# VDD.net
KiCad netlist of a schematic drawn in Altium Designer
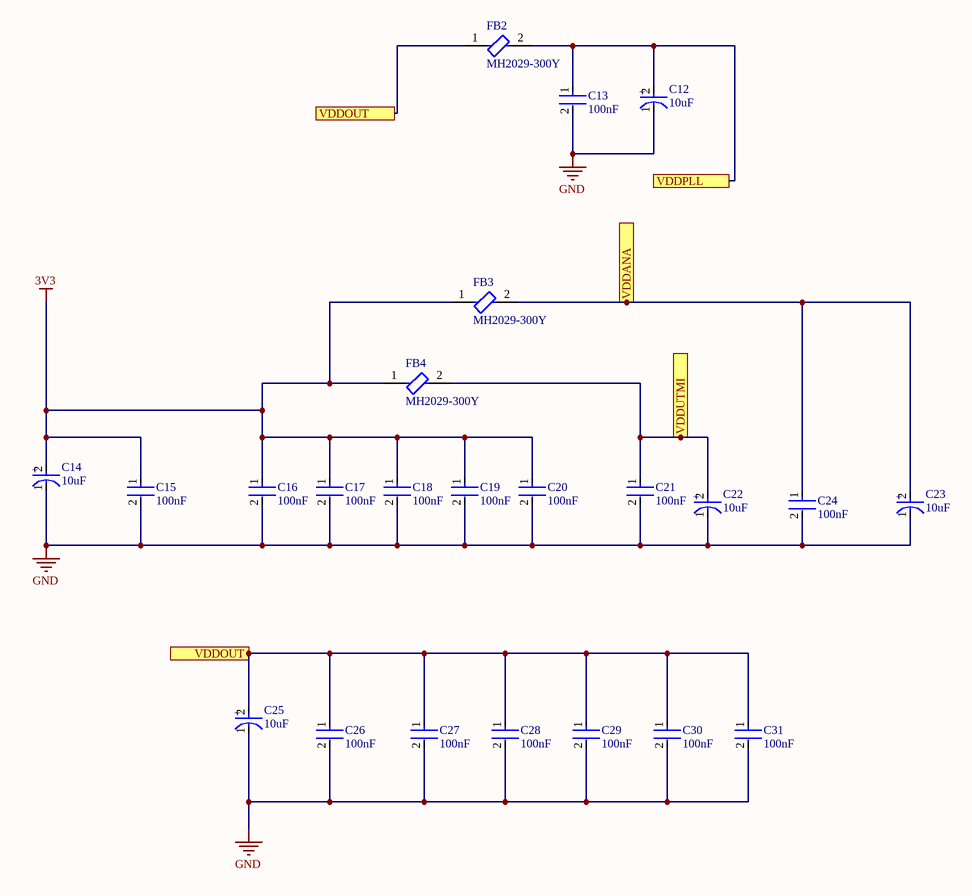
[diagram p0:  VDD.SchDoc]

(export (version "E")
  (design (tool "Eeschema 10.0.6"))
  (components
    (comp (ref "C12")
      (value "10uF")
      (footprint "FP-TAJP-MFG")
      (description "10uF 10V  ±20% 6Ω 0805  SMD Tantalum Capacitor")
      (fields (field (name "TOLERANCE") "20%") (field (name "VOLTAGE") "10V"))
      (libsource (lib "Altium Content Vault") (part "a00bbbee19879c290e62620ae7e47b1"))
    )
    (comp (ref "C13")
      (value "100nF")
      (footprint "FP-0805-L_2_01_0_2-W_1_25-IPC_B")
      (description "General Purpose Ceramic Capacitor, 0805, 100nF, 10%, X7R, 15%, 100V")
      (fields (field (name "VOLTAGE") "100V") (field (name "TOLERANCE") "10%"))
      (libsource (lib "Altium Content Vault") (part "b4654b650e69147ec39a6b967a45e02"))
    )
    (comp (ref "C14")
      (value "10uF")
      (footprint "FP-TAJP-MFG")
      (description "10uF 10V  ±20% 6Ω 0805  SMD Tantalum Capacitor")
      (fields (field (name "TOLERANCE") "20%") (field (name "VOLTAGE") "10V"))
      (libsource (lib "Altium Content Vault") (part "a00bbbee19879c290e62620ae7e47b1"))
    )
    (comp (ref "C15")
      (value "100nF")
      (footprint "FP-0805-L_2_01_0_2-W_1_25-IPC_B")
      (description "General Purpose Ceramic Capacitor, 0805, 100nF, 10%, X7R, 15%, 100V")
      (fields (field (name "VOLTAGE") "100V") (field (name "TOLERANCE") "10%"))
      (libsource (lib "Altium Content Vault") (part "b4654b650e69147ec39a6b967a45e02"))
    )
    (comp (ref "C16")
      (value "100nF")
      (footprint "FP-0805-L_2_01_0_2-W_1_25-IPC_B")
      (description "General Purpose Ceramic Capacitor, 0805, 100nF, 10%, X7R, 15%, 100V")
      (fields (field (name "VOLTAGE") "100V") (field (name "TOLERANCE") "10%"))
      (libsource (lib "Altium Content Vault") (part "b4654b650e69147ec39a6b967a45e02"))
    )
    (comp (ref "C17")
      (value "100nF")
      (footprint "FP-0805-L_2_01_0_2-W_1_25-IPC_B")
      (description "General Purpose Ceramic Capacitor, 0805, 100nF, 10%, X7R, 15%, 100V")
      (fields (field (name "VOLTAGE") "100V") (field (name "TOLERANCE") "10%"))
      (libsource (lib "Altium Content Vault") (part "b4654b650e69147ec39a6b967a45e02"))
    )
    (comp (ref "C18")
      (value "100nF")
      (footprint "FP-0805-L_2_01_0_2-W_1_25-IPC_B")
      (description "General Purpose Ceramic Capacitor, 0805, 100nF, 10%, X7R, 15%, 100V")
      (fields (field (name "VOLTAGE") "100V") (field (name "TOLERANCE") "10%"))
      (libsource (lib "Altium Content Vault") (part "b4654b650e69147ec39a6b967a45e02"))
    )
    (comp (ref "C19")
      (value "100nF")
      (footprint "FP-0805-L_2_01_0_2-W_1_25-IPC_B")
      (description "General Purpose Ceramic Capacitor, 0805, 100nF, 10%, X7R, 15%, 100V")
      (fields (field (name "VOLTAGE") "100V") (field (name "TOLERANCE") "10%"))
      (libsource (lib "Altium Content Vault") (part "b4654b650e69147ec39a6b967a45e02"))
    )
    (comp (ref "C20")
      (value "100nF")
      (footprint "FP-0805-L_2_01_0_2-W_1_25-IPC_B")
      (description "General Purpose Ceramic Capacitor, 0805, 100nF, 10%, X7R, 15%, 100V")
      (fields (field (name "VOLTAGE") "100V") (field (name "TOLERANCE") "10%"))
      (libsource (lib "Altium Content Vault") (part "b4654b650e69147ec39a6b967a45e02"))
    )
    (comp (ref "C21")
      (value "100nF")
      (footprint "FP-0805-L_2_01_0_2-W_1_25-IPC_B")
      (description "General Purpose Ceramic Capacitor, 0805, 100nF, 10%, X7R, 15%, 100V")
      (fields (field (name "VOLTAGE") "100V") (field (name "TOLERANCE") "10%"))
      (libsource (lib "Altium Content Vault") (part "b4654b650e69147ec39a6b967a45e02"))
    )
    (comp (ref "C22")
      (value "10uF")
      (footprint "FP-TAJP-MFG")
      (description "10uF 10V  ±20% 6Ω 0805  SMD Tantalum Capacitor")
      (fields (field (name "TOLERANCE") "20%") (field (name "VOLTAGE") "10V"))
      (libsource (lib "Altium Content Vault") (part "a00bbbee19879c290e62620ae7e47b1"))
    )
    (comp (ref "C23")
      (value "10uF")
      (footprint "FP-TAJP-MFG")
      (description "10uF 10V  ±20% 6Ω 0805  SMD Tantalum Capacitor")
      (fields (field (name "TOLERANCE") "20%") (field (name "VOLTAGE") "10V"))
      (libsource (lib "Altium Content Vault") (part "a00bbbee19879c290e62620ae7e47b1"))
    )
    (comp (ref "C24")
      (value "100nF")
      (footprint "FP-0805-L_2_01_0_2-W_1_25-IPC_B")
      (description "General Purpose Ceramic Capacitor, 0805, 100nF, 10%, X7R, 15%, 100V")
      (fields (field (name "VOLTAGE") "100V") (field (name "TOLERANCE") "10%"))
      (libsource (lib "Altium Content Vault") (part "b4654b650e69147ec39a6b967a45e02"))
    )
    (comp (ref "C25")
      (value "10uF")
      (footprint "FP-TAJP-MFG")
      (description "10uF 10V  ±20% 6Ω 0805  SMD Tantalum Capacitor")
      (fields (field (name "TOLERANCE") "20%") (field (name "VOLTAGE") "10V"))
      (libsource (lib "Altium Content Vault") (part "a00bbbee19879c290e62620ae7e47b1"))
    )
    (comp (ref "C26")
      (value "100nF")
      (footprint "FP-0805-L_2_01_0_2-W_1_25-IPC_B")
      (description "General Purpose Ceramic Capacitor, 0805, 100nF, 10%, X7R, 15%, 100V")
      (fields (field (name "VOLTAGE") "100V") (field (name "TOLERANCE") "10%"))
      (libsource (lib "Altium Content Vault") (part "b4654b650e69147ec39a6b967a45e02"))
    )
    (comp (ref "C27")
      (value "100nF")
      (footprint "FP-0805-L_2_01_0_2-W_1_25-IPC_B")
      (description "General Purpose Ceramic Capacitor, 0805, 100nF, 10%, X7R, 15%, 100V")
      (fields (field (name "VOLTAGE") "100V") (field (name "TOLERANCE") "10%"))
      (libsource (lib "Altium Content Vault") (part "b4654b650e69147ec39a6b967a45e02"))
    )
    (comp (ref "C28")
      (value "100nF")
      (footprint "FP-0805-L_2_01_0_2-W_1_25-IPC_B")
      (description "General Purpose Ceramic Capacitor, 0805, 100nF, 10%, X7R, 15%, 100V")
      (fields (field (name "VOLTAGE") "100V") (field (name "TOLERANCE") "10%"))
      (libsource (lib "Altium Content Vault") (part "b4654b650e69147ec39a6b967a45e02"))
    )
    (comp (ref "C29")
      (value "100nF")
      (footprint "FP-0805-L_2_01_0_2-W_1_25-IPC_B")
      (description "General Purpose Ceramic Capacitor, 0805, 100nF, 10%, X7R, 15%, 100V")
      (fields (field (name "VOLTAGE") "100V") (field (name "TOLERANCE") "10%"))
      (libsource (lib "Altium Content Vault") (part "b4654b650e69147ec39a6b967a45e02"))
    )
    (comp (ref "C30")
      (value "100nF")
      (footprint "FP-0805-L_2_01_0_2-W_1_25-IPC_B")
      (description "General Purpose Ceramic Capacitor, 0805, 100nF, 10%, X7R, 15%, 100V")
      (fields (field (name "VOLTAGE") "100V") (field (name "TOLERANCE") "10%"))
      (libsource (lib "Altium Content Vault") (part "b4654b650e69147ec39a6b967a45e02"))
    )
    (comp (ref "C31")
      (value "100nF")
      (footprint "FP-0805-L_2_01_0_2-W_1_25-IPC_B")
      (description "General Purpose Ceramic Capacitor, 0805, 100nF, 10%, X7R, 15%, 100V")
      (fields (field (name "VOLTAGE") "100V") (field (name "TOLERANCE") "10%"))
      (libsource (lib "Altium Content Vault") (part "b4654b650e69147ec39a6b967a45e02"))
    )
    (comp (ref "FB2")
      (value "MH2029-300Y")
      (footprint "FP-MH2029-MFG")
      (description "FERRITE BEAD 30 OHM 0805 1LN")
      (fields
        (field (name "OCTOPART") "https://octopart.com/mh2029-300y-bourns-756929")
        (field (name "MANUFACTURER") "Bourns")
      )
      (libsource (lib "Altium Content Vault") (part "5f30dd21d616792df468990f7003faa"))
    )
    (comp (ref "FB3")
      (value "MH2029-300Y")
      (footprint "FP-MH2029-MFG")
      (description "FERRITE BEAD 30 OHM 0805 1LN")
      (fields
        (field (name "OCTOPART") "https://octopart.com/mh2029-300y-bourns-756929")
        (field (name "MANUFACTURER") "Bourns")
      )
      (libsource (lib "Altium Content Vault") (part "5f30dd21d616792df468990f7003faa"))
    )
    (comp (ref "FB4")
      (value "MH2029-300Y")
      (footprint "FP-MH2029-MFG")
      (description "FERRITE BEAD 30 OHM 0805 1LN")
      (fields
        (field (name "OCTOPART") "https://octopart.com/mh2029-300y-bourns-756929")
        (field (name "MANUFACTURER") "Bourns")
      )
      (libsource (lib "Altium Content Vault") (part "5f30dd21d616792df468990f7003faa"))
    )
  )
  (nets
    (net (code "1") (name "/VDDANA") (class "Default")
      (node (ref "C23") (pin "2") (pinfunction "A_2") (pintype "passive"))
      (node (ref "C24") (pin "1") (pinfunction "1_1") (pintype "passive"))
      (node (ref "FB3") (pin "2") (pinfunction "2_2") (pintype "passive"))
    )
    (net (code "2") (name "/VDDOUT") (class "Default")
      (node (ref "C25") (pin "2") (pinfunction "A_2") (pintype "passive"))
      (node (ref "C26") (pin "1") (pinfunction "1_1") (pintype "passive"))
      (node (ref "C27") (pin "1") (pinfunction "1_1") (pintype "passive"))
      (node (ref "C28") (pin "1") (pinfunction "1_1") (pintype "passive"))
      (node (ref "C29") (pin "1") (pinfunction "1_1") (pintype "passive"))
      (node (ref "C30") (pin "1") (pinfunction "1_1") (pintype "passive"))
      (node (ref "C31") (pin "1") (pinfunction "1_1") (pintype "passive"))
      (node (ref "FB2") (pin "1") (pinfunction "1_1") (pintype "passive"))
    )
    (net (code "3") (name "/VDDPLL") (class "Default")
      (node (ref "C12") (pin "2") (pinfunction "A_2") (pintype "passive"))
      (node (ref "C13") (pin "1") (pinfunction "1_1") (pintype "passive"))
      (node (ref "FB2") (pin "2") (pinfunction "2_2") (pintype "passive"))
    )
    (net (code "4") (name "/VDDUTMI") (class "Default")
      (node (ref "C21") (pin "1") (pinfunction "1_1") (pintype "passive"))
      (node (ref "C22") (pin "2") (pinfunction "A_2") (pintype "passive"))
      (node (ref "FB4") (pin "2") (pinfunction "2_2") (pintype "passive"))
    )
    (net (code "5") (name "3V3") (class "Default")
      (node (ref "C14") (pin "2") (pinfunction "A_2") (pintype "passive"))
      (node (ref "C15") (pin "1") (pinfunction "1_1") (pintype "passive"))
      (node (ref "C16") (pin "1") (pinfunction "1_1") (pintype "passive"))
      (node (ref "C17") (pin "1") (pinfunction "1_1") (pintype "passive"))
      (node (ref "C18") (pin "1") (pinfunction "1_1") (pintype "passive"))
      (node (ref "C19") (pin "1") (pinfunction "1_1") (pintype "passive"))
      (node (ref "C20") (pin "1") (pinfunction "1_1") (pintype "passive"))
      (node (ref "FB3") (pin "1") (pinfunction "1_1") (pintype "passive"))
      (node (ref "FB4") (pin "1") (pinfunction "1_1") (pintype "passive"))
    )
    (net (code "6") (name "GND") (class "Default")
      (node (ref "C12") (pin "1") (pinfunction "C_1") (pintype "passive"))
      (node (ref "C13") (pin "2") (pinfunction "2_2") (pintype "passive"))
      (node (ref "C14") (pin "1") (pinfunction "C_1") (pintype "passive"))
      (node (ref "C15") (pin "2") (pinfunction "2_2") (pintype "passive"))
      (node (ref "C16") (pin "2") (pinfunction "2_2") (pintype "passive"))
      (node (ref "C17") (pin "2") (pinfunction "2_2") (pintype "passive"))
      (node (ref "C18") (pin "2") (pinfunction "2_2") (pintype "passive"))
      (node (ref "C19") (pin "2") (pinfunction "2_2") (pintype "passive"))
      (node (ref "C20") (pin "2") (pinfunction "2_2") (pintype "passive"))
      (node (ref "C21") (pin "2") (pinfunction "2_2") (pintype "passive"))
      (node (ref "C22") (pin "1") (pinfunction "C_1") (pintype "passive"))
      (node (ref "C23") (pin "1") (pinfunction "C_1") (pintype "passive"))
      (node (ref "C24") (pin "2") (pinfunction "2_2") (pintype "passive"))
      (node (ref "C25") (pin "1") (pinfunction "C_1") (pintype "passive"))
      (node (ref "C26") (pin "2") (pinfunction "2_2") (pintype "passive"))
      (node (ref "C27") (pin "2") (pinfunction "2_2") (pintype "passive"))
      (node (ref "C28") (pin "2") (pinfunction "2_2") (pintype "passive"))
      (node (ref "C29") (pin "2") (pinfunction "2_2") (pintype "passive"))
      (node (ref "C30") (pin "2") (pinfunction "2_2") (pintype "passive"))
      (node (ref "C31") (pin "2") (pinfunction "2_2") (pintype "passive"))
    )
  )
)
